# digital_sensor.net
KiCad netlist of a schematic drawn in EAGLE
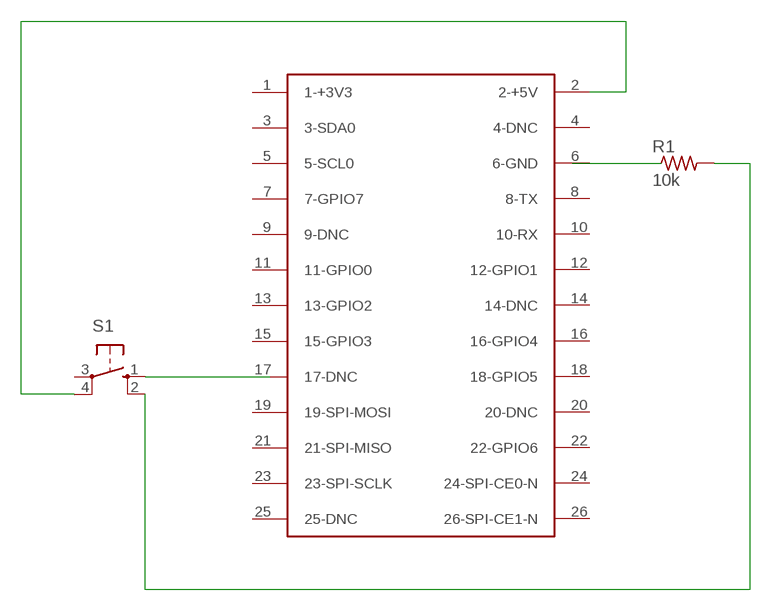
[diagram p0: schematic, sheet 1]

(export (version "E")
  (design (tool "Eeschema 10.0.6"))
  (components
    (comp (ref "R1")
      (value "10k")
      (footprint "eagle-import:0207_12")
      (libsource (lib "eagle-import") (part "R-US_0207/12"))
    )
    (comp (ref "S1")
      (value "40-XX-ROUND")
      (footprint "eagle-import:B3F-40XX-ROUND")
      (libsource (lib "eagle-import") (part "40-XX-ROUND"))
    )
    (comp (ref "U$1")
      (value "RASPBERRY-PI")
      (footprint "eagle-import:RASPBERRY-PI")
      (libsource (lib "eagle-import") (part "RASPBERRY-PI"))
    )
  )
  (nets
    (net (code "1") (name "Net-(S1-P1)") (class "Default")
      (node (ref "S1") (pin "4") (pinfunction "P1_4") (pintype "passive"))
      (node (ref "U$1") (pin "2") (pinfunction "2-+5V_2") (pintype "bidirectional"))
    )
    (net (code "2") (name "Net-(S1-S1)") (class "Default")
      (node (ref "R1") (pin "2") (pinfunction "2_2") (pintype "passive"))
      (node (ref "S1") (pin "2") (pinfunction "S1_2") (pintype "passive"))
    )
    (net (code "3") (name "unconnected-(R1-Pad1)") (class "Default")
      (node (ref "R1") (pin "1") (pinfunction "1_1") (pintype "passive"))
    )
    (net (code "4") (name "unconnected-(S1-P-Pad3)") (class "Default")
      (node (ref "S1") (pin "3") (pinfunction "P_3") (pintype "passive"))
    )
    (net (code "5") (name "unconnected-(S1-S-Pad1)") (class "Default")
      (node (ref "S1") (pin "1") (pinfunction "S_1") (pintype "passive"))
    )
    (net (code "6") (name "unconnected-(U$1-1-+3V3-Pad1)") (class "Default")
      (node (ref "U$1") (pin "1") (pinfunction "1-+3V3_1") (pintype "bidirectional"))
    )
    (net (code "7") (name "unconnected-(U$1-3-SDA0-Pad3)") (class "Default")
      (node (ref "U$1") (pin "3") (pinfunction "3-SDA0_3") (pintype "bidirectional"))
    )
    (net (code "8") (name "unconnected-(U$1-4-DNC-Pad4)") (class "Default")
      (node (ref "U$1") (pin "4") (pinfunction "4-DNC_4") (pintype "bidirectional"))
    )
    (net (code "9") (name "unconnected-(U$1-5-SCL0-Pad5)") (class "Default")
      (node (ref "U$1") (pin "5") (pinfunction "5-SCL0_5") (pintype "bidirectional"))
    )
    (net (code "10") (name "unconnected-(U$1-6-GND-Pad6)") (class "Default")
      (node (ref "U$1") (pin "6") (pinfunction "6-GND_6") (pintype "bidirectional"))
    )
    (net (code "11") (name "unconnected-(U$1-7-GPIO7-Pad7)") (class "Default")
      (node (ref "U$1") (pin "7") (pinfunction "7-GPIO7_7") (pintype "bidirectional"))
    )
    (net (code "12") (name "unconnected-(U$1-8-TX-Pad8)") (class "Default")
      (node (ref "U$1") (pin "8") (pinfunction "8-TX_8") (pintype "bidirectional"))
    )
    (net (code "13") (name "unconnected-(U$1-9-DNC-Pad9)") (class "Default")
      (node (ref "U$1") (pin "9") (pinfunction "9-DNC_9") (pintype "bidirectional"))
    )
    (net (code "14") (name "unconnected-(U$1-10-RX-Pad10)") (class "Default")
      (node (ref "U$1") (pin "10") (pinfunction "10-RX_10") (pintype "bidirectional"))
    )
    (net (code "15") (name "unconnected-(U$1-11-GPIO0-Pad11)") (class "Default")
      (node (ref "U$1") (pin "11") (pinfunction "11-GPIO0_11") (pintype "bidirectional"))
    )
    (net (code "16") (name "unconnected-(U$1-12-GPIO1-Pad12)") (class "Default")
      (node (ref "U$1") (pin "12") (pinfunction "12-GPIO1_12") (pintype "bidirectional"))
    )
    (net (code "17") (name "unconnected-(U$1-13-GPIO2-Pad13)") (class "Default")
      (node (ref "U$1") (pin "13") (pinfunction "13-GPIO2_13") (pintype "bidirectional"))
    )
    (net (code "18") (name "unconnected-(U$1-14-DNC-Pad14)") (class "Default")
      (node (ref "U$1") (pin "14") (pinfunction "14-DNC_14") (pintype "bidirectional"))
    )
    (net (code "19") (name "unconnected-(U$1-15-GPIO3-Pad15)") (class "Default")
      (node (ref "U$1") (pin "15") (pinfunction "15-GPIO3_15") (pintype "bidirectional"))
    )
    (net (code "20") (name "unconnected-(U$1-16-GPIO4-Pad16)") (class "Default")
      (node (ref "U$1") (pin "16") (pinfunction "16-GPIO4_16") (pintype "bidirectional"))
    )
    (net (code "21") (name "unconnected-(U$1-17-DNC-Pad17)") (class "Default")
      (node (ref "U$1") (pin "17") (pinfunction "17-DNC_17") (pintype "bidirectional"))
    )
    (net (code "22") (name "unconnected-(U$1-18-GPIO5-Pad18)") (class "Default")
      (node (ref "U$1") (pin "18") (pinfunction "18-GPIO5_18") (pintype "bidirectional"))
    )
    (net (code "23") (name "unconnected-(U$1-19-SPI-MOSI-Pad19)") (class "Default")
      (node (ref "U$1") (pin "19") (pinfunction "19-SPI-MOSI_19") (pintype "bidirectional"))
    )
    (net (code "24") (name "unconnected-(U$1-20-DNC-Pad20)") (class "Default")
      (node (ref "U$1") (pin "20") (pinfunction "20-DNC_20") (pintype "bidirectional"))
    )
    (net (code "25") (name "unconnected-(U$1-21-SPI-MISO-Pad21)") (class "Default")
      (node (ref "U$1") (pin "21") (pinfunction "21-SPI-MISO_21") (pintype "bidirectional"))
    )
    (net (code "26") (name "unconnected-(U$1-22-GPIO6-Pad22)") (class "Default")
      (node (ref "U$1") (pin "22") (pinfunction "22-GPIO6_22") (pintype "bidirectional"))
    )
    (net (code "27") (name "unconnected-(U$1-23-SPI-SCLK-Pad23)") (class "Default")
      (node (ref "U$1") (pin "23") (pinfunction "23-SPI-SCLK_23") (pintype "bidirectional"))
    )
    (net (code "28") (name "unconnected-(U$1-24-SPI-CE0-N-Pad24)") (class "Default")
      (node (ref "U$1") (pin "24") (pinfunction "24-SPI-CE0-N_24") (pintype "bidirectional"))
    )
    (net (code "29") (name "unconnected-(U$1-25-DNC-Pad25)") (class "Default")
      (node (ref "U$1") (pin "25") (pinfunction "25-DNC_25") (pintype "bidirectional"))
    )
    (net (code "30") (name "unconnected-(U$1-26-SPI-CE1-N-Pad26)") (class "Default")
      (node (ref "U$1") (pin "26") (pinfunction "26-SPI-CE1-N_26") (pintype "bidirectional"))
    )
  )
)
